# GameBone.net
KiCad netlist of a schematic drawn in EAGLE
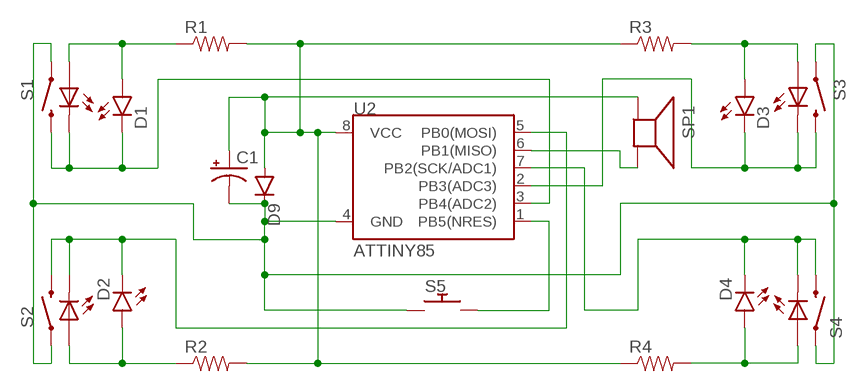
[diagram p0: schematic, sheet 1]

(export (version "E")
  (design (tool "Eeschema 10.0.6"))
  (components
    (comp (ref "C1")
      (value "10UF-25V-20%(PTH)")
      (footprint "eagle-import:CPOL-RADIAL-10UF-25V")
      (libsource (lib "eagle-import") (part "10UF-25V-20%(PTH)"))
    )
    (comp (ref "D1")
      (value "LED5MM")
      (footprint "eagle-import:LED5MM")
      (libsource (lib "eagle-import") (part "LED5MM"))
    )
    (comp (ref "D2")
      (value "LED5MM")
      (footprint "eagle-import:LED5MM")
      (libsource (lib "eagle-import") (part "LED5MM"))
    )
    (comp (ref "D3")
      (value "LED5MM")
      (footprint "eagle-import:LED5MM")
      (libsource (lib "eagle-import") (part "LED5MM"))
    )
    (comp (ref "D4")
      (value "LED5MM")
      (footprint "eagle-import:LED5MM")
      (libsource (lib "eagle-import") (part "LED5MM"))
    )
    (comp (ref "D9")
      (value "DIODEPTH")
      (footprint "eagle-import:DIODE-1N4001")
      (libsource (lib "eagle-import") (part "DIODEPTH"))
    )
    (comp (ref "R1")
      (value "RESISTORPTH-1/4W")
      (footprint "eagle-import:AXIAL-0.4")
      (libsource (lib "eagle-import") (part "RESISTORPTH-1/4W"))
    )
    (comp (ref "R2")
      (value "RESISTORPTH-1/4W")
      (footprint "eagle-import:AXIAL-0.4")
      (libsource (lib "eagle-import") (part "RESISTORPTH-1/4W"))
    )
    (comp (ref "R3")
      (value "RESISTORPTH-1/4W")
      (footprint "eagle-import:AXIAL-0.4")
      (libsource (lib "eagle-import") (part "RESISTORPTH-1/4W"))
    )
    (comp (ref "R4")
      (value "RESISTORPTH-1/4W")
      (footprint "eagle-import:AXIAL-0.4")
      (libsource (lib "eagle-import") (part "RESISTORPTH-1/4W"))
    )
    (comp (ref "S1")
      (value "SWITCH-MOMENTARY-LEDPTH")
      (footprint "eagle-import:TACTILE-PTH-LED-12MM")
      (libsource (lib "eagle-import") (part "SWITCH-MOMENTARY-LEDPTH"))
    )
    (comp (ref "S2")
      (value "SWITCH-MOMENTARY-LEDPTH")
      (footprint "eagle-import:TACTILE-PTH-LED-12MM")
      (libsource (lib "eagle-import") (part "SWITCH-MOMENTARY-LEDPTH"))
    )
    (comp (ref "S3")
      (value "SWITCH-MOMENTARY-LEDPTH")
      (footprint "eagle-import:TACTILE-PTH-LED-12MM")
      (libsource (lib "eagle-import") (part "SWITCH-MOMENTARY-LEDPTH"))
    )
    (comp (ref "S4")
      (value "SWITCH-MOMENTARY-LEDPTH")
      (footprint "eagle-import:TACTILE-PTH-LED-12MM")
      (libsource (lib "eagle-import") (part "SWITCH-MOMENTARY-LEDPTH"))
    )
    (comp (ref "S5")
      (value "SWITCH_PUSHBUTTONEVQ-PE")
      (footprint "eagle-import:TACT_PANA-EVQ")
      (libsource (lib "eagle-import") (part "SWITCH_PUSHBUTTONEVQ-PE"))
    )
    (comp (ref "SP1")
      (value "SPEAKER/AL60P")
      (footprint "eagle-import:AL60P")
      (libsource (lib "eagle-import") (part "SPEAKER/AL60P"))
    )
    (comp (ref "U2")
      (value "ATTINY85")
      (footprint "eagle-import:DIP08")
      (libsource (lib "eagle-import") (part "ATTINY45TINY85-20-DIP"))
    )
  )
  (nets
    (net (code "1") (name "Net-(C1-+)") (class "Default")
      (node (ref "C1") (pin "1") (pinfunction "+_1") (pintype "passive"))
      (node (ref "D9") (pin "A") (pinfunction "A_A") (pintype "passive"))
      (node (ref "R1") (pin "P$2") (pinfunction "2_P$2") (pintype "passive"))
      (node (ref "R2") (pin "P$2") (pinfunction "2_P$2") (pintype "passive"))
      (node (ref "R3") (pin "P$1") (pinfunction "1_P$1") (pintype "passive"))
      (node (ref "R4") (pin "P$1") (pinfunction "1_P$1") (pintype "passive"))
      (node (ref "SP1") (pin "1") (pinfunction "+_1") (pintype "passive"))
      (node (ref "U2") (pin "8") (pinfunction "VCC_8") (pintype "bidirectional"))
    )
    (net (code "2") (name "Net-(C1--)") (class "Default")
      (node (ref "C1") (pin "2") (pinfunction "-_2") (pintype "passive"))
      (node (ref "D9") (pin "C") (pinfunction "C_C") (pintype "passive"))
      (node (ref "S1") (pin "4") (pinfunction "1_4") (pintype "passive"))
      (node (ref "S2") (pin "4") (pinfunction "1_4") (pintype "passive"))
      (node (ref "S3") (pin "4") (pinfunction "1_4") (pintype "passive"))
      (node (ref "S4") (pin "4") (pinfunction "1_4") (pintype "passive"))
      (node (ref "S5") (pin "P$1") (pinfunction "P$1_P$1") (pintype "passive"))
      (node (ref "U2") (pin "4") (pinfunction "GND_4") (pintype "bidirectional"))
    )
    (net (code "3") (name "Net-(D1-C)") (class "Default")
      (node (ref "D1") (pin "K") (pinfunction "C_K") (pintype "passive"))
      (node (ref "S1") (pin "2") (pinfunction "2_2") (pintype "passive"))
      (node (ref "S1") (pin "C") (pinfunction "C_C") (pintype "passive"))
      (node (ref "U2") (pin "3") (pinfunction "PB4(ADC2)_3") (pintype "bidirectional"))
    )
    (net (code "4") (name "Net-(D2-C)") (class "Default")
      (node (ref "D2") (pin "K") (pinfunction "C_K") (pintype "passive"))
      (node (ref "S2") (pin "2") (pinfunction "2_2") (pintype "passive"))
      (node (ref "S2") (pin "C") (pinfunction "C_C") (pintype "passive"))
      (node (ref "U2") (pin "5") (pinfunction "PB0(MOSI)_5") (pintype "bidirectional"))
    )
    (net (code "5") (name "Net-(D3-C)") (class "Default")
      (node (ref "D3") (pin "K") (pinfunction "C_K") (pintype "passive"))
      (node (ref "S3") (pin "2") (pinfunction "2_2") (pintype "passive"))
      (node (ref "S3") (pin "C") (pinfunction "C_C") (pintype "passive"))
      (node (ref "U2") (pin "2") (pinfunction "PB3(ADC3)_2") (pintype "bidirectional"))
    )
    (net (code "6") (name "Net-(D4-C)") (class "Default")
      (node (ref "D4") (pin "K") (pinfunction "C_K") (pintype "passive"))
      (node (ref "S4") (pin "2") (pinfunction "2_2") (pintype "passive"))
      (node (ref "S4") (pin "C") (pinfunction "C_C") (pintype "passive"))
      (node (ref "U2") (pin "7") (pinfunction "PB2(SCK/ADC1)_7") (pintype "bidirectional"))
    )
    (net (code "7") (name "Net-(R1-1)") (class "Default")
      (node (ref "D1") (pin "A") (pinfunction "A_A") (pintype "passive"))
      (node (ref "R1") (pin "P$1") (pinfunction "1_P$1") (pintype "passive"))
      (node (ref "S1") (pin "A") (pinfunction "A_A") (pintype "passive"))
    )
    (net (code "8") (name "Net-(R2-1)") (class "Default")
      (node (ref "D2") (pin "A") (pinfunction "A_A") (pintype "passive"))
      (node (ref "R2") (pin "P$1") (pinfunction "1_P$1") (pintype "passive"))
      (node (ref "S2") (pin "A") (pinfunction "A_A") (pintype "passive"))
    )
    (net (code "9") (name "Net-(R3-2)") (class "Default")
      (node (ref "D3") (pin "A") (pinfunction "A_A") (pintype "passive"))
      (node (ref "R3") (pin "P$2") (pinfunction "2_P$2") (pintype "passive"))
      (node (ref "S3") (pin "A") (pinfunction "A_A") (pintype "passive"))
    )
    (net (code "10") (name "Net-(R4-2)") (class "Default")
      (node (ref "D4") (pin "A") (pinfunction "A_A") (pintype "passive"))
      (node (ref "R4") (pin "P$2") (pinfunction "2_P$2") (pintype "passive"))
      (node (ref "S4") (pin "A") (pinfunction "A_A") (pintype "passive"))
    )
    (net (code "11") (name "Net-(SP1--)") (class "Default")
      (node (ref "SP1") (pin "2") (pinfunction "-_2") (pintype "passive"))
      (node (ref "U2") (pin "6") (pinfunction "PB1(MISO)_6") (pintype "bidirectional"))
    )
    (net (code "12") (name "Net-(U2-PB5(NRES))") (class "Default")
      (node (ref "S5") (pin "P$2") (pinfunction "P$2_P$2") (pintype "passive"))
      (node (ref "U2") (pin "1") (pinfunction "PB5(NRES)_1") (pintype "bidirectional"))
    )
  )
)
